# module_SX1272.net
KiCad netlist of a schematic drawn in EAGLE
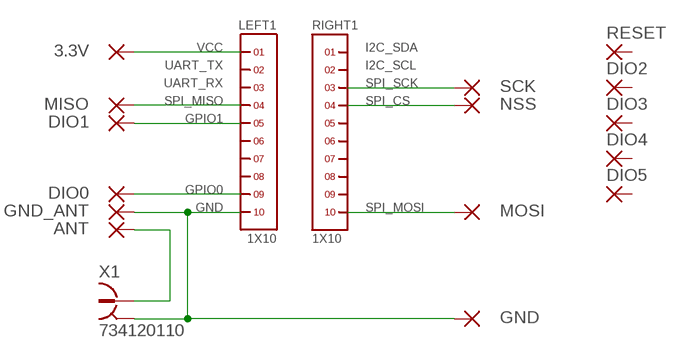
[diagram p0: schematic, sheet 1]

(export (version "E")
  (design (tool "Eeschema 10.0.6"))
  (components
    (comp (ref "3.3V")
      (value "SMD1")
      (footprint "eagle-import:SMD0,65-1,27")
      (libsource (lib "eagle-import") (part "SMD1"))
    )
    (comp (ref "ANT")
      (value "SMD1")
      (footprint "eagle-import:SMD0,65-1,27")
      (libsource (lib "eagle-import") (part "SMD1"))
    )
    (comp (ref "DIO0")
      (value "SMD1")
      (footprint "eagle-import:SMD0,65-1,27")
      (libsource (lib "eagle-import") (part "SMD1"))
    )
    (comp (ref "DIO1")
      (value "SMD1")
      (footprint "eagle-import:SMD0,65-1,27")
      (libsource (lib "eagle-import") (part "SMD1"))
    )
    (comp (ref "DIO2")
      (value "SMD1")
      (footprint "eagle-import:SMD0,65-1,27")
      (libsource (lib "eagle-import") (part "SMD1"))
    )
    (comp (ref "DIO3")
      (value "SMD1")
      (footprint "eagle-import:SMD0,65-1,27")
      (libsource (lib "eagle-import") (part "SMD1"))
    )
    (comp (ref "DIO4")
      (value "SMD1")
      (footprint "eagle-import:SMD0,65-1,27")
      (libsource (lib "eagle-import") (part "SMD1"))
    )
    (comp (ref "DIO5")
      (value "SMD1")
      (footprint "eagle-import:SMD0,65-1,27")
      (libsource (lib "eagle-import") (part "SMD1"))
    )
    (comp (ref "GND")
      (value "SMD1")
      (footprint "eagle-import:SMD0,65-1,27")
      (libsource (lib "eagle-import") (part "SMD1"))
    )
    (comp (ref "GND_ANT")
      (value "SMD1")
      (footprint "eagle-import:SMD0,65-1,27")
      (libsource (lib "eagle-import") (part "SMD1"))
    )
    (comp (ref "LEFT1")
      (value "1X10")
      (footprint "eagle-import:1X10")
      (libsource (lib "eagle-import") (part "1X10"))
    )
    (comp (ref "MISO")
      (value "SMD1")
      (footprint "eagle-import:SMD0,65-1,27")
      (libsource (lib "eagle-import") (part "SMD1"))
    )
    (comp (ref "MOSI")
      (value "SMD1")
      (footprint "eagle-import:SMD0,65-1,27")
      (libsource (lib "eagle-import") (part "SMD1"))
    )
    (comp (ref "NSS")
      (value "SMD1")
      (footprint "eagle-import:SMD0,65-1,27")
      (libsource (lib "eagle-import") (part "SMD1"))
    )
    (comp (ref "RESET")
      (value "SMD1")
      (footprint "eagle-import:SMD0,65-1,27")
      (libsource (lib "eagle-import") (part "SMD1"))
    )
    (comp (ref "RIGHT1")
      (value "1X10")
      (footprint "eagle-import:1X10")
      (libsource (lib "eagle-import") (part "1X10"))
    )
    (comp (ref "SCK")
      (value "SMD1")
      (footprint "eagle-import:SMD0,65-1,27")
      (libsource (lib "eagle-import") (part "SMD1"))
    )
    (comp (ref "X1")
      (value "734120110")
      (footprint "eagle-import:734120110")
      (libsource (lib "eagle-import") (part "734120110"))
    )
  )
  (nets
    (net (code "1") (name "Net-(3.3V-P)") (class "Default")
      (node (ref "3.3V") (pin "1") (pinfunction "P_1") (pintype "passive"))
      (node (ref "LEFT1") (pin "1") (pinfunction "1_1") (pintype "bidirectional"))
    )
    (net (code "2") (name "Net-(ANT-P)") (class "Default")
      (node (ref "ANT") (pin "1") (pinfunction "P_1") (pintype "passive"))
      (node (ref "X1") (pin "1") (pinfunction "1_1") (pintype "passive"))
    )
    (net (code "3") (name "Net-(DIO0-P)") (class "Default")
      (node (ref "DIO0") (pin "1") (pinfunction "P_1") (pintype "passive"))
      (node (ref "LEFT1") (pin "9") (pinfunction "9_9") (pintype "bidirectional"))
    )
    (net (code "4") (name "Net-(DIO1-P)") (class "Default")
      (node (ref "DIO1") (pin "1") (pinfunction "P_1") (pintype "passive"))
      (node (ref "LEFT1") (pin "5") (pinfunction "5_5") (pintype "bidirectional"))
    )
    (net (code "5") (name "Net-(GND-P)") (class "Default")
      (node (ref "GND") (pin "1") (pinfunction "P_1") (pintype "passive"))
      (node (ref "GND_ANT") (pin "1") (pinfunction "P_1") (pintype "passive"))
      (node (ref "LEFT1") (pin "10") (pinfunction "10_10") (pintype "bidirectional"))
      (node (ref "X1") (pin "S@1") (pinfunction "2_S@1") (pintype "passive"))
      (node (ref "X1") (pin "S@2") (pinfunction "2_S@2") (pintype "passive"))
      (node (ref "X1") (pin "S@3") (pinfunction "2_S@3") (pintype "passive"))
    )
    (net (code "6") (name "Net-(MISO-P)") (class "Default")
      (node (ref "LEFT1") (pin "4") (pinfunction "4_4") (pintype "bidirectional"))
      (node (ref "MISO") (pin "1") (pinfunction "P_1") (pintype "passive"))
    )
    (net (code "7") (name "Net-(MOSI-P)") (class "Default")
      (node (ref "MOSI") (pin "1") (pinfunction "P_1") (pintype "passive"))
      (node (ref "RIGHT1") (pin "10") (pinfunction "10_10") (pintype "bidirectional"))
    )
    (net (code "8") (name "Net-(NSS-P)") (class "Default")
      (node (ref "NSS") (pin "1") (pinfunction "P_1") (pintype "passive"))
      (node (ref "RIGHT1") (pin "4") (pinfunction "4_4") (pintype "bidirectional"))
    )
    (net (code "9") (name "Net-(SCK-P)") (class "Default")
      (node (ref "RIGHT1") (pin "3") (pinfunction "3_3") (pintype "bidirectional"))
      (node (ref "SCK") (pin "1") (pinfunction "P_1") (pintype "passive"))
    )
    (net (code "10") (name "unconnected-(DIO2-P-Pad1)") (class "Default")
      (node (ref "DIO2") (pin "1") (pinfunction "P_1") (pintype "passive"))
    )
    (net (code "11") (name "unconnected-(DIO3-P-Pad1)") (class "Default")
      (node (ref "DIO3") (pin "1") (pinfunction "P_1") (pintype "passive"))
    )
    (net (code "12") (name "unconnected-(DIO4-P-Pad1)") (class "Default")
      (node (ref "DIO4") (pin "1") (pinfunction "P_1") (pintype "passive"))
    )
    (net (code "13") (name "unconnected-(DIO5-P-Pad1)") (class "Default")
      (node (ref "DIO5") (pin "1") (pinfunction "P_1") (pintype "passive"))
    )
    (net (code "14") (name "unconnected-(LEFT1-Pad2)") (class "Default")
      (node (ref "LEFT1") (pin "2") (pinfunction "2_2") (pintype "bidirectional"))
    )
    (net (code "15") (name "unconnected-(LEFT1-Pad3)") (class "Default")
      (node (ref "LEFT1") (pin "3") (pinfunction "3_3") (pintype "bidirectional"))
    )
    (net (code "16") (name "unconnected-(LEFT1-Pad6)") (class "Default")
      (node (ref "LEFT1") (pin "6") (pinfunction "6_6") (pintype "bidirectional"))
    )
    (net (code "17") (name "unconnected-(LEFT1-Pad7)") (class "Default")
      (node (ref "LEFT1") (pin "7") (pinfunction "7_7") (pintype "bidirectional"))
    )
    (net (code "18") (name "unconnected-(LEFT1-Pad8)") (class "Default")
      (node (ref "LEFT1") (pin "8") (pinfunction "8_8") (pintype "bidirectional"))
    )
    (net (code "19") (name "unconnected-(RESET-P-Pad1)") (class "Default")
      (node (ref "RESET") (pin "1") (pinfunction "P_1") (pintype "passive"))
    )
    (net (code "20") (name "unconnected-(RIGHT1-Pad1)") (class "Default")
      (node (ref "RIGHT1") (pin "1") (pinfunction "1_1") (pintype "bidirectional"))
    )
    (net (code "21") (name "unconnected-(RIGHT1-Pad2)") (class "Default")
      (node (ref "RIGHT1") (pin "2") (pinfunction "2_2") (pintype "bidirectional"))
    )
    (net (code "22") (name "unconnected-(RIGHT1-Pad5)") (class "Default")
      (node (ref "RIGHT1") (pin "5") (pinfunction "5_5") (pintype "bidirectional"))
    )
    (net (code "23") (name "unconnected-(RIGHT1-Pad6)") (class "Default")
      (node (ref "RIGHT1") (pin "6") (pinfunction "6_6") (pintype "bidirectional"))
    )
    (net (code "24") (name "unconnected-(RIGHT1-Pad7)") (class "Default")
      (node (ref "RIGHT1") (pin "7") (pinfunction "7_7") (pintype "bidirectional"))
    )
    (net (code "25") (name "unconnected-(RIGHT1-Pad8)") (class "Default")
      (node (ref "RIGHT1") (pin "8") (pinfunction "8_8") (pintype "bidirectional"))
    )
    (net (code "26") (name "unconnected-(RIGHT1-Pad9)") (class "Default")
      (node (ref "RIGHT1") (pin "9") (pinfunction "9_9") (pintype "bidirectional"))
    )
  )
)
